# orienteering_clock_rev2.net
KiCad netlist of a schematic drawn in EAGLE
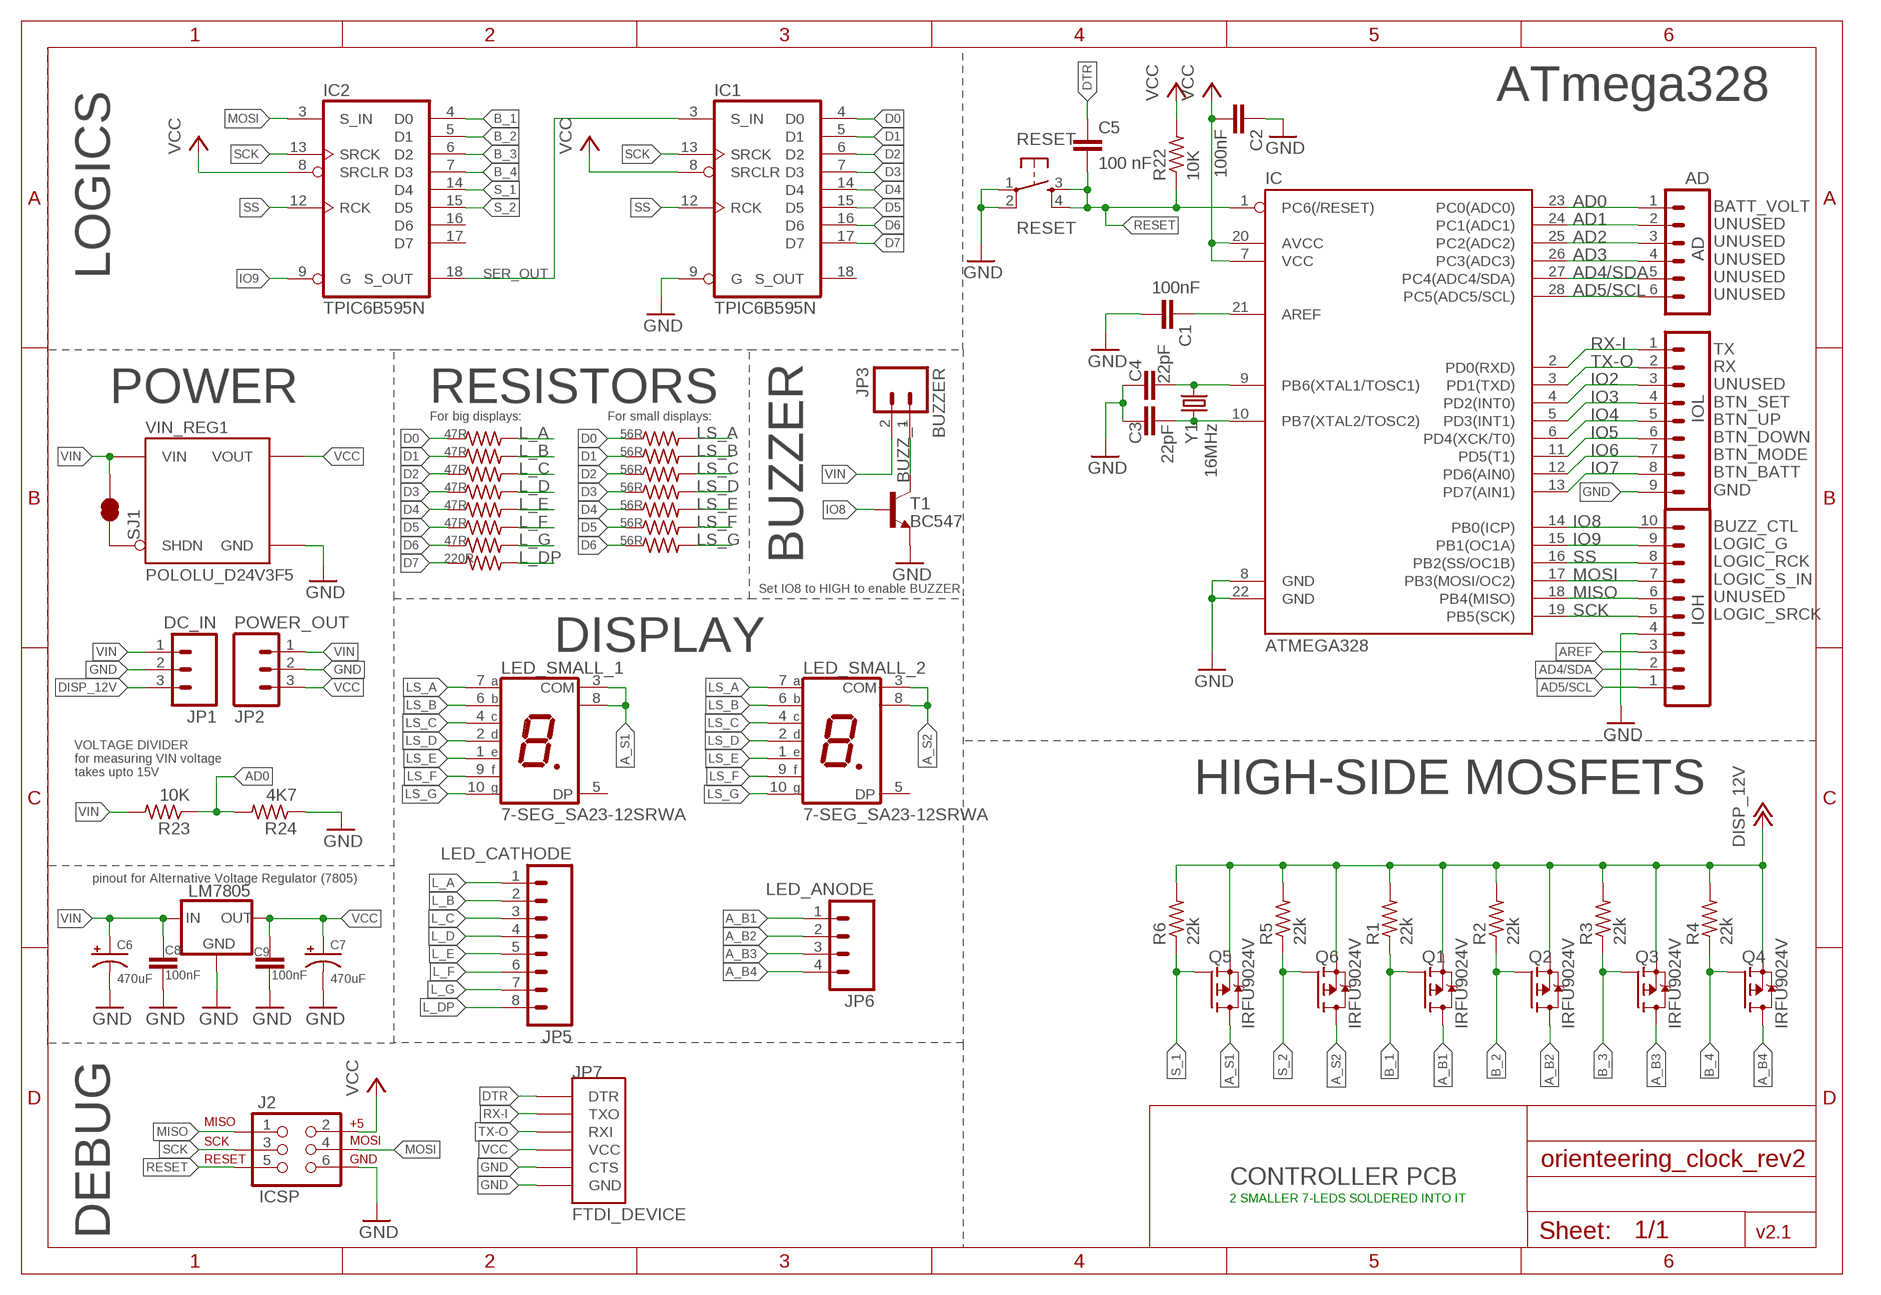
[diagram p0: schematic, sheet 1]

(export (version "E")
  (design (tool "Eeschema 10.0.6"))
  (components
    (comp (ref "AD")
      (value "AD")
      (footprint "eagle-import:1X06-SIP_LOCK")
      (libsource (lib "eagle-import") (part "M06SIP_LOCK"))
    )
    (comp (ref "C1")
      (value "100nF")
      (footprint "eagle-import:CAP-PTH-SMALL")
      (libsource (lib "eagle-import") (part "CAPPTH"))
    )
    (comp (ref "C2")
      (value "100nF")
      (footprint "eagle-import:CAP-PTH-SMALL")
      (libsource (lib "eagle-import") (part "CAPPTH"))
    )
    (comp (ref "C3")
      (value "22pF")
      (footprint "eagle-import:CAP-PTH-SMALL")
      (libsource (lib "eagle-import") (part "SparkFun-Capacitors_CAPPTH"))
    )
    (comp (ref "C4")
      (value "22pF")
      (footprint "eagle-import:CAP-PTH-SMALL")
      (libsource (lib "eagle-import") (part "SparkFun-Capacitors_CAPPTH"))
    )
    (comp (ref "C5")
      (value "100 nF")
      (footprint "eagle-import:CAP-PTH-SMALL")
      (libsource (lib "eagle-import") (part "CAPPTH"))
    )
    (comp (ref "C6")
      (value "470uF")
      (footprint "eagle-import:CPOL-RADIAL-100UF-25V")
      (libsource (lib "eagle-import") (part "CAP_POLPTH1"))
    )
    (comp (ref "C7")
      (value "470uF")
      (footprint "eagle-import:CPOL-RADIAL-100UF-25V")
      (libsource (lib "eagle-import") (part "CAP_POLPTH1"))
    )
    (comp (ref "C8")
      (value "100nF")
      (footprint "eagle-import:CAP-PTH-SMALL")
      (libsource (lib "eagle-import") (part "SparkFun-Passives_CAPPTH"))
    )
    (comp (ref "C9")
      (value "100nF")
      (footprint "eagle-import:CAP-PTH-SMALL")
      (libsource (lib "eagle-import") (part "SparkFun-Passives_CAPPTH"))
    )
    (comp (ref "IC")
      (value "ATMEGA328")
      (footprint "eagle-import:DIL28-3")
      (libsource (lib "eagle-import") (part "ATMEGA328P_PDIP"))
    )
    (comp (ref "IC1")
      (value "TPIC6B595N")
      (footprint "eagle-import:DIL20")
      (libsource (lib "eagle-import") (part "TPIC6B595N"))
    )
    (comp (ref "IC2")
      (value "TPIC6B595N")
      (footprint "eagle-import:DIL20")
      (libsource (lib "eagle-import") (part "TPIC6B595N"))
    )
    (comp (ref "IOH")
      (value "M10LOCK")
      (footprint "eagle-import:1X10_LOCK")
      (libsource (lib "eagle-import") (part "M10LOCK"))
    )
    (comp (ref "IOL")
      (value "M09LOCK")
      (footprint "eagle-import:1X09_LOCK")
      (libsource (lib "eagle-import") (part "M09LOCK"))
    )
    (comp (ref "J2")
      (value "ICSP")
      (footprint "eagle-import:2X3_LOCK")
      (libsource (lib "eagle-import") (part "AVR_SPI_PRG_62X3_LOCK"))
    )
    (comp (ref "JP1")
      (value "DC_IN")
      (footprint "eagle-import:MOLEX-1X3")
      (libsource (lib "eagle-import") (part "M03POLAR"))
    )
    (comp (ref "JP2")
      (value "POWER_OUT")
      (footprint "eagle-import:1X03_LOCK")
      (libsource (lib "eagle-import") (part "M03LOCK"))
    )
    (comp (ref "JP3")
      (value "BUZZER")
      (footprint "eagle-import:1X02_LOCK")
      (libsource (lib "eagle-import") (part "M02LOCK"))
    )
    (comp (ref "JP5")
      (value "LED_CATHODE")
      (footprint "eagle-import:1X08_ROUND")
      (libsource (lib "eagle-import") (part "M08"))
    )
    (comp (ref "JP6")
      (value "LED_ANODE")
      (footprint "eagle-import:1X04")
      (libsource (lib "eagle-import") (part "M04PTH"))
    )
    (comp (ref "JP7")
      (value "FTDI_DEVICE")
      (footprint "eagle-import:FTDI_DEVICE_SIDE")
      (libsource (lib "eagle-import") (part "FTDI_DEVICE"))
    )
    (comp (ref "LED_SMALL_1")
      (value "7-SEG_SA23-12SRWA")
      (footprint "eagle-import:SA23-12SRWA")
      (libsource (lib "eagle-import") (part "7-SEG_SA23-12SRWA"))
    )
    (comp (ref "LED_SMALL_2")
      (value "7-SEG_SA23-12SRWA")
      (footprint "eagle-import:SA23-12SRWA")
      (libsource (lib "eagle-import") (part "7-SEG_SA23-12SRWA"))
    )
    (comp (ref "LM7805")
      (value "78XXS")
      (footprint "eagle-import:78XXS")
      (libsource (lib "eagle-import") (part "78XXS"))
    )
    (comp (ref "Q1")
      (value "IRFU9024V")
      (footprint "eagle-import:TO251AA-V")
      (libsource (lib "eagle-import") (part "IRFU9024V"))
    )
    (comp (ref "Q2")
      (value "IRFU9024V")
      (footprint "eagle-import:TO251AA-V")
      (libsource (lib "eagle-import") (part "IRFU9024V"))
    )
    (comp (ref "Q3")
      (value "IRFU9024V")
      (footprint "eagle-import:TO251AA-V")
      (libsource (lib "eagle-import") (part "IRFU9024V"))
    )
    (comp (ref "Q4")
      (value "IRFU9024V")
      (footprint "eagle-import:TO251AA-V")
      (libsource (lib "eagle-import") (part "IRFU9024V"))
    )
    (comp (ref "Q5")
      (value "IRFU9024V")
      (footprint "eagle-import:TO251AA-V")
      (libsource (lib "eagle-import") (part "IRFU9024V"))
    )
    (comp (ref "Q6")
      (value "IRFU9024V")
      (footprint "eagle-import:TO251AA-V")
      (libsource (lib "eagle-import") (part "IRFU9024V"))
    )
    (comp (ref "R1")
      (value "22k")
      (footprint "eagle-import:0207_5V")
      (libsource (lib "eagle-import") (part "R-US_0207/5V"))
    )
    (comp (ref "R2")
      (value "22k")
      (footprint "eagle-import:0207_5V")
      (libsource (lib "eagle-import") (part "R-US_0207/5V"))
    )
    (comp (ref "R3")
      (value "22k")
      (footprint "eagle-import:0207_5V")
      (libsource (lib "eagle-import") (part "R-US_0207/5V"))
    )
    (comp (ref "R4")
      (value "22k")
      (footprint "eagle-import:0207_5V")
      (libsource (lib "eagle-import") (part "R-US_0207/5V"))
    )
    (comp (ref "R5")
      (value "22k")
      (footprint "eagle-import:0207_5V")
      (libsource (lib "eagle-import") (part "R-US_0207/5V"))
    )
    (comp (ref "R6")
      (value "22k")
      (footprint "eagle-import:0207_5V")
      (libsource (lib "eagle-import") (part "R-US_0207/5V"))
    )
    (comp (ref "R7")
      (value "47R")
      (footprint "eagle-import:0207_10")
      (libsource (lib "eagle-import") (part "R-US_0207/10"))
    )
    (comp (ref "R8")
      (value "47R")
      (footprint "eagle-import:0207_10")
      (libsource (lib "eagle-import") (part "R-US_0207/10"))
    )
    (comp (ref "R9")
      (value "47R")
      (footprint "eagle-import:0207_10")
      (libsource (lib "eagle-import") (part "R-US_0207/10"))
    )
    (comp (ref "R10")
      (value "47R")
      (footprint "eagle-import:0207_10")
      (libsource (lib "eagle-import") (part "R-US_0207/10"))
    )
    (comp (ref "R11")
      (value "47R")
      (footprint "eagle-import:0207_10")
      (libsource (lib "eagle-import") (part "R-US_0207/10"))
    )
    (comp (ref "R12")
      (value "47R")
      (footprint "eagle-import:0207_10")
      (libsource (lib "eagle-import") (part "R-US_0207/10"))
    )
    (comp (ref "R13")
      (value "47R")
      (footprint "eagle-import:0207_10")
      (libsource (lib "eagle-import") (part "R-US_0207/10"))
    )
    (comp (ref "R14")
      (value "56R")
      (footprint "eagle-import:0207_10")
      (libsource (lib "eagle-import") (part "R-US_0207/10"))
    )
    (comp (ref "R15")
      (value "56R")
      (footprint "eagle-import:0207_10")
      (libsource (lib "eagle-import") (part "R-US_0207/10"))
    )
    (comp (ref "R16")
      (value "56R")
      (footprint "eagle-import:0207_10")
      (libsource (lib "eagle-import") (part "R-US_0207/10"))
    )
    (comp (ref "R17")
      (value "56R")
      (footprint "eagle-import:0207_10")
      (libsource (lib "eagle-import") (part "R-US_0207/10"))
    )
    (comp (ref "R18")
      (value "56R")
      (footprint "eagle-import:0207_10")
      (libsource (lib "eagle-import") (part "R-US_0207/10"))
    )
    (comp (ref "R19")
      (value "56R")
      (footprint "eagle-import:0207_10")
      (libsource (lib "eagle-import") (part "R-US_0207/10"))
    )
    (comp (ref "R20")
      (value "56R")
      (footprint "eagle-import:0207_10")
      (libsource (lib "eagle-import") (part "R-US_0207/10"))
    )
    (comp (ref "R21")
      (value "220R")
      (footprint "eagle-import:0207_10")
      (libsource (lib "eagle-import") (part "R-US_0207/10"))
    )
    (comp (ref "R22")
      (value "10K")
      (footprint "eagle-import:0207_10")
      (libsource (lib "eagle-import") (part "R-US_0207/10"))
    )
    (comp (ref "R23")
      (value "10K")
      (footprint "eagle-import:0207_10")
      (libsource (lib "eagle-import") (part "R-US_0207/10"))
    )
    (comp (ref "R24")
      (value "4K7")
      (footprint "eagle-import:0207_10")
      (libsource (lib "eagle-import") (part "R-US_0207/10"))
    )
    (comp (ref "RESET")
      (value "RESET")
      (footprint "eagle-import:TACTILE-PTH")
      (libsource (lib "eagle-import") (part "TAC_SWITCHPTH"))
    )
    (comp (ref "SJ1")
      (value "SHDN_PULLUP")
      (footprint "eagle-import:PAD-JUMPER-2-NC_BY_TRACE_YES_SILK")
      (libsource (lib "eagle-import") (part "JUMPER-PAD-2-NC_BY_TRACE"))
    )
    (comp (ref "T1")
      (value "BC547")
      (footprint "eagle-import:TO92")
      (libsource (lib "eagle-import") (part "BC547"))
    )
    (comp (ref "VIN_REG1")
      (value "POLOLU_D24V3F5")
      (footprint "eagle-import:POLOLU_D24V3F_HC")
      (libsource (lib "eagle-import") (part "POLOLU_D24V3F-HC5"))
    )
    (comp (ref "Y1")
      (value "16MHz")
      (footprint "eagle-import:HC49US")
      (libsource (lib "eagle-import") (part "CRYSTALHC49US"))
    )
  )
  (nets
    (net (code "1") (name "/AD1") (class "Default")
      (node (ref "AD") (pin "2") (pinfunction "2_2") (pintype "passive"))
      (node (ref "IC") (pin "24") (pinfunction "PC1(ADC1)_24") (pintype "bidirectional"))
    )
    (net (code "2") (name "/AD2") (class "Default")
      (node (ref "AD") (pin "3") (pinfunction "3_3") (pintype "passive"))
      (node (ref "IC") (pin "25") (pinfunction "PC2(ADC2)_25") (pintype "bidirectional"))
    )
    (net (code "3") (name "/AD3") (class "Default")
      (node (ref "AD") (pin "4") (pinfunction "4_4") (pintype "passive"))
      (node (ref "IC") (pin "26") (pinfunction "PC3(ADC3)_26") (pintype "bidirectional"))
    )
    (net (code "4") (name "/BUZZ_-") (class "Default")
      (node (ref "JP3") (pin "1") (pinfunction "1_1") (pintype "passive"))
      (node (ref "T1") (pin "3") (pinfunction "C_3") (pintype "passive"))
    )
    (net (code "5") (name "/IO2") (class "Default")
      (node (ref "IC") (pin "4") (pinfunction "PD2(INT0)_4") (pintype "bidirectional"))
      (node (ref "IOL") (pin "3") (pinfunction "3_3") (pintype "passive"))
    )
    (net (code "6") (name "/IO3") (class "Default")
      (node (ref "IC") (pin "5") (pinfunction "PD3(INT1)_5") (pintype "bidirectional"))
      (node (ref "IOL") (pin "4") (pinfunction "4_4") (pintype "passive"))
    )
    (net (code "7") (name "/IO4") (class "Default")
      (node (ref "IC") (pin "6") (pinfunction "PD4(XCK/T0)_6") (pintype "bidirectional"))
      (node (ref "IOL") (pin "5") (pinfunction "5_5") (pintype "passive"))
    )
    (net (code "8") (name "/IO5") (class "Default")
      (node (ref "IC") (pin "11") (pinfunction "PD5(T1)_11") (pintype "bidirectional"))
      (node (ref "IOL") (pin "6") (pinfunction "6_6") (pintype "passive"))
    )
    (net (code "9") (name "/IO6") (class "Default")
      (node (ref "IC") (pin "12") (pinfunction "PD6(AIN0)_12") (pintype "bidirectional"))
      (node (ref "IOL") (pin "7") (pinfunction "7_7") (pintype "passive"))
    )
    (net (code "10") (name "/IO7") (class "Default")
      (node (ref "IC") (pin "13") (pinfunction "PD7(AIN1)_13") (pintype "bidirectional"))
      (node (ref "IOL") (pin "8") (pinfunction "8_8") (pintype "passive"))
    )
    (net (code "11") (name "/SER_OUT") (class "Default")
      (node (ref "IC1") (pin "3") (pinfunction "S_IN_3") (pintype "input"))
      (node (ref "IC2") (pin "18") (pinfunction "S_OUT_18") (pintype "tri_state"))
    )
    (net (code "12") (name "AD0") (class "Default")
      (node (ref "AD") (pin "1") (pinfunction "1_1") (pintype "passive"))
      (node (ref "IC") (pin "23") (pinfunction "PC0(ADC0)_23") (pintype "bidirectional"))
      (node (ref "R23") (pin "1") (pinfunction "1_1") (pintype "passive"))
      (node (ref "R24") (pin "2") (pinfunction "2_2") (pintype "passive"))
    )
    (net (code "13") (name "AD4{slash}SDA") (class "Default")
      (node (ref "AD") (pin "5") (pinfunction "5_5") (pintype "passive"))
      (node (ref "IC") (pin "27") (pinfunction "PC4(ADC4/SDA)_27") (pintype "bidirectional"))
      (node (ref "IOH") (pin "2") (pinfunction "2_2") (pintype "passive"))
    )
    (net (code "14") (name "AD5{slash}SCL") (class "Default")
      (node (ref "AD") (pin "6") (pinfunction "6_6") (pintype "passive"))
      (node (ref "IC") (pin "28") (pinfunction "PC5(ADC5/SCL)_28") (pintype "bidirectional"))
      (node (ref "IOH") (pin "1") (pinfunction "1_1") (pintype "passive"))
    )
    (net (code "15") (name "AREF") (class "Default")
      (node (ref "C1") (pin "1") (pinfunction "1_1") (pintype "passive"))
      (node (ref "IC") (pin "21") (pinfunction "AREF_21") (pintype "bidirectional"))
      (node (ref "IOH") (pin "3") (pinfunction "3_3") (pintype "passive"))
    )
    (net (code "16") (name "A_B1") (class "Default")
      (node (ref "JP6") (pin "1") (pinfunction "1_1") (pintype "passive"))
      (node (ref "Q1") (pin "2") (pinfunction "D_2") (pintype "passive"))
    )
    (net (code "17") (name "A_B2") (class "Default")
      (node (ref "JP6") (pin "2") (pinfunction "2_2") (pintype "passive"))
      (node (ref "Q2") (pin "2") (pinfunction "D_2") (pintype "passive"))
    )
    (net (code "18") (name "A_B3") (class "Default")
      (node (ref "JP6") (pin "3") (pinfunction "3_3") (pintype "passive"))
      (node (ref "Q3") (pin "2") (pinfunction "D_2") (pintype "passive"))
    )
    (net (code "19") (name "A_B4") (class "Default")
      (node (ref "JP6") (pin "4") (pinfunction "4_4") (pintype "passive"))
      (node (ref "Q4") (pin "2") (pinfunction "D_2") (pintype "passive"))
    )
    (net (code "20") (name "A_S1") (class "Default")
      (node (ref "LED_SMALL_1") (pin "3") (pinfunction "COM_3") (pintype "passive"))
      (node (ref "LED_SMALL_1") (pin "8") (pinfunction "COM_8") (pintype "passive"))
      (node (ref "Q5") (pin "2") (pinfunction "D_2") (pintype "passive"))
    )
    (net (code "21") (name "A_S2") (class "Default")
      (node (ref "LED_SMALL_2") (pin "3") (pinfunction "COM_3") (pintype "passive"))
      (node (ref "LED_SMALL_2") (pin "8") (pinfunction "COM_8") (pintype "passive"))
      (node (ref "Q6") (pin "2") (pinfunction "D_2") (pintype "passive"))
    )
    (net (code "22") (name "B_1") (class "Default")
      (node (ref "IC2") (pin "4") (pinfunction "D0_4") (pintype "tri_state"))
      (node (ref "Q1") (pin "1") (pinfunction "G_1") (pintype "passive"))
      (node (ref "R1") (pin "1") (pinfunction "1_1") (pintype "passive"))
    )
    (net (code "23") (name "B_2") (class "Default")
      (node (ref "IC2") (pin "5") (pinfunction "D1_5") (pintype "tri_state"))
      (node (ref "Q2") (pin "1") (pinfunction "G_1") (pintype "passive"))
      (node (ref "R2") (pin "1") (pinfunction "1_1") (pintype "passive"))
    )
    (net (code "24") (name "B_3") (class "Default")
      (node (ref "IC2") (pin "6") (pinfunction "D2_6") (pintype "tri_state"))
      (node (ref "Q3") (pin "1") (pinfunction "G_1") (pintype "passive"))
      (node (ref "R3") (pin "1") (pinfunction "1_1") (pintype "passive"))
    )
    (net (code "25") (name "B_4") (class "Default")
      (node (ref "IC2") (pin "7") (pinfunction "D3_7") (pintype "tri_state"))
      (node (ref "Q4") (pin "1") (pinfunction "G_1") (pintype "passive"))
      (node (ref "R4") (pin "1") (pinfunction "1_1") (pintype "passive"))
    )
    (net (code "26") (name "D0") (class "Default")
      (node (ref "IC1") (pin "4") (pinfunction "D0_4") (pintype "tri_state"))
      (node (ref "R14") (pin "1") (pinfunction "1_1") (pintype "passive"))
      (node (ref "R7") (pin "1") (pinfunction "1_1") (pintype "passive"))
    )
    (net (code "27") (name "D1") (class "Default")
      (node (ref "IC1") (pin "5") (pinfunction "D1_5") (pintype "tri_state"))
      (node (ref "R15") (pin "1") (pinfunction "1_1") (pintype "passive"))
      (node (ref "R8") (pin "1") (pinfunction "1_1") (pintype "passive"))
    )
    (net (code "28") (name "D2") (class "Default")
      (node (ref "IC1") (pin "6") (pinfunction "D2_6") (pintype "tri_state"))
      (node (ref "R16") (pin "1") (pinfunction "1_1") (pintype "passive"))
      (node (ref "R9") (pin "1") (pinfunction "1_1") (pintype "passive"))
    )
    (net (code "29") (name "D3") (class "Default")
      (node (ref "IC1") (pin "7") (pinfunction "D3_7") (pintype "tri_state"))
      (node (ref "R10") (pin "1") (pinfunction "1_1") (pintype "passive"))
      (node (ref "R17") (pin "1") (pinfunction "1_1") (pintype "passive"))
    )
    (net (code "30") (name "D4") (class "Default")
      (node (ref "IC1") (pin "14") (pinfunction "D4_14") (pintype "tri_state"))
      (node (ref "R11") (pin "1") (pinfunction "1_1") (pintype "passive"))
      (node (ref "R18") (pin "1") (pinfunction "1_1") (pintype "passive"))
    )
    (net (code "31") (name "D5") (class "Default")
      (node (ref "IC1") (pin "15") (pinfunction "D5_15") (pintype "tri_state"))
      (node (ref "R12") (pin "1") (pinfunction "1_1") (pintype "passive"))
      (node (ref "R19") (pin "1") (pinfunction "1_1") (pintype "passive"))
    )
    (net (code "32") (name "D6") (class "Default")
      (node (ref "IC1") (pin "16") (pinfunction "D6_16") (pintype "tri_state"))
      (node (ref "R13") (pin "1") (pinfunction "1_1") (pintype "passive"))
      (node (ref "R20") (pin "1") (pinfunction "1_1") (pintype "passive"))
    )
    (net (code "33") (name "D7") (class "Default")
      (node (ref "IC1") (pin "17") (pinfunction "D7_17") (pintype "tri_state"))
      (node (ref "R21") (pin "1") (pinfunction "1_1") (pintype "passive"))
    )
    (net (code "34") (name "DISP_12V") (class "Default")
      (node (ref "JP1") (pin "3") (pinfunction "3_3") (pintype "passive"))
      (node (ref "Q1") (pin "3") (pinfunction "S_3") (pintype "passive"))
      (node (ref "Q2") (pin "3") (pinfunction "S_3") (pintype "passive"))
      (node (ref "Q3") (pin "3") (pinfunction "S_3") (pintype "passive"))
      (node (ref "Q4") (pin "3") (pinfunction "S_3") (pintype "passive"))
      (node (ref "Q5") (pin "3") (pinfunction "S_3") (pintype "passive"))
      (node (ref "Q6") (pin "3") (pinfunction "S_3") (pintype "passive"))
      (node (ref "R1") (pin "2") (pinfunction "2_2") (pintype "passive"))
      (node (ref "R2") (pin "2") (pinfunction "2_2") (pintype "passive"))
      (node (ref "R3") (pin "2") (pinfunction "2_2") (pintype "passive"))
      (node (ref "R4") (pin "2") (pinfunction "2_2") (pintype "passive"))
      (node (ref "R5") (pin "2") (pinfunction "2_2") (pintype "passive"))
      (node (ref "R6") (pin "2") (pinfunction "2_2") (pintype "passive"))
    )
    (net (code "35") (name "DTR") (class "Default")
      (node (ref "C5") (pin "1") (pinfunction "1_1") (pintype "passive"))
      (node (ref "JP7") (pin "P$1") (pinfunction "DTR_P$1") (pintype "bidirectional"))
    )
    (net (code "36") (name "GND") (class "Default")
      (node (ref "C1") (pin "2") (pinfunction "2_2") (pintype "passive"))
      (node (ref "C2") (pin "1") (pinfunction "1_1") (pintype "passive"))
      (node (ref "C3") (pin "1") (pinfunction "1_1") (pintype "passive"))
      (node (ref "C4") (pin "1") (pinfunction "1_1") (pintype "passive"))
      (node (ref "C6") (pin "2") (pinfunction "-_2") (pintype "passive"))
      (node (ref "C7") (pin "2") (pinfunction "-_2") (pintype "passive"))
      (node (ref "C8") (pin "2") (pinfunction "2_2") (pintype "passive"))
      (node (ref "C9") (pin "2") (pinfunction "2_2") (pintype "passive"))
      (node (ref "IC") (pin "22") (pinfunction "GND_22") (pintype "bidirectional"))
      (node (ref "IC") (pin "8") (pinfunction "GND_8") (pintype "bidirectional"))
      (node (ref "IC1") (pin "9") (pinfunction "G_9") (pintype "input"))
      (node (ref "IOH") (pin "4") (pinfunction "4_4") (pintype "passive"))
      (node (ref "IOL") (pin "9") (pinfunction "9_9") (pintype "passive"))
      (node (ref "J2") (pin "6") (pinfunction "6_6") (pintype "passive"))
      (node (ref "JP1") (pin "2") (pinfunction "2_2") (pintype "passive"))
      (node (ref "JP2") (pin "2") (pinfunction "2_2") (pintype "passive"))
      (node (ref "JP7") (pin "P$5") (pinfunction "CTS_P$5") (pintype "bidirectional"))
      (node (ref "JP7") (pin "P$6") (pinfunction "GND_P$6") (pintype "bidirectional"))
      (node (ref "LM7805") (pin "GND") (pinfunction "GND_GND") (pintype "input"))
      (node (ref "R24") (pin "1") (pinfunction "1_1") (pintype "passive"))
      (node (ref "RESET") (pin "1") (pinfunction "1_1") (pintype "passive"))
      (node (ref "RESET") (pin "2") (pinfunction "2_2") (pintype "passive"))
      (node (ref "T1") (pin "1") (pinfunction "E_1") (pintype "passive"))
      (node (ref "VIN_REG1") (pin "G") (pinfunction "GND_G") (pintype "power_in"))
    )
    (net (code "37") (name "IO8") (class "Default")
      (node (ref "IC") (pin "14") (pinfunction "PB0(ICP)_14") (pintype "bidirectional"))
      (node (ref "IOH") (pin "10") (pinfunction "10_10") (pintype "passive"))
      (node (ref "T1") (pin "2") (pinfunction "B_2") (pintype "passive"))
    )
    (net (code "38") (name "IO9") (class "Default")
      (node (ref "IC") (pin "15") (pinfunction "PB1(OC1A)_15") (pintype "bidirectional"))
      (node (ref "IC2") (pin "9") (pinfunction "G_9") (pintype "input"))
      (node (ref "IOH") (pin "9") (pinfunction "9_9") (pintype "passive"))
    )
    (net (code "39") (name "LS_A") (class "Default")
      (node (ref "LED_SMALL_1") (pin "7") (pinfunction "A_7") (pintype "passive"))
      (node (ref "LED_SMALL_2") (pin "7") (pinfunction "A_7") (pintype "passive"))
      (node (ref "R14") (pin "2") (pinfunction "2_2") (pintype "passive"))
    )
    (net (code "40") (name "LS_B") (class "Default")
      (node (ref "LED_SMALL_1") (pin "6") (pinfunction "B_6") (pintype "passive"))
      (node (ref "LED_SMALL_2") (pin "6") (pinfunction "B_6") (pintype "passive"))
      (node (ref "R15") (pin "2") (pinfunction "2_2") (pintype "passive"))
    )
    (net (code "41") (name "LS_C") (class "Default")
      (node (ref "LED_SMALL_1") (pin "4") (pinfunction "C_4") (pintype "passive"))
      (node (ref "LED_SMALL_2") (pin "4") (pinfunction "C_4") (pintype "passive"))
      (node (ref "R16") (pin "2") (pinfunction "2_2") (pintype "passive"))
    )
    (net (code "42") (name "LS_D") (class "Default")
      (node (ref "LED_SMALL_1") (pin "2") (pinfunction "D_2") (pintype "passive"))
      (node (ref "LED_SMALL_2") (pin "2") (pinfunction "D_2") (pintype "passive"))
      (node (ref "R17") (pin "2") (pinfunction "2_2") (pintype "passive"))
    )
    (net (code "43") (name "LS_E") (class "Default")
      (node (ref "LED_SMALL_1") (pin "1") (pinfunction "E_1") (pintype "passive"))
      (node (ref "LED_SMALL_2") (pin "1") (pinfunction "E_1") (pintype "passive"))
      (node (ref "R18") (pin "2") (pinfunction "2_2") (pintype "passive"))
    )
    (net (code "44") (name "LS_F") (class "Default")
      (node (ref "LED_SMALL_1") (pin "9") (pinfunction "F_9") (pintype "passive"))
      (node (ref "LED_SMALL_2") (pin "9") (pinfunction "F_9") (pintype "passive"))
      (node (ref "R19") (pin "2") (pinfunction "2_2") (pintype "passive"))
    )
    (net (code "45") (name "LS_G") (class "Default")
      (node (ref "LED_SMALL_1") (pin "10") (pinfunction "G_10") (pintype "passive"))
      (node (ref "LED_SMALL_2") (pin "10") (pinfunction "G_10") (pintype "passive"))
      (node (ref "R20") (pin "2") (pinfunction "2_2") (pintype "passive"))
    )
    (net (code "46") (name "L_A") (class "Default")
      (node (ref "JP5") (pin "1") (pinfunction "1_1") (pintype "passive"))
      (node (ref "R7") (pin "2") (pinfunction "2_2") (pintype "passive"))
    )
    (net (code "47") (name "L_B") (class "Default")
      (node (ref "JP5") (pin "2") (pinfunction "2_2") (pintype "passive"))
      (node (ref "R8") (pin "2") (pinfunction "2_2") (pintype "passive"))
    )
    (net (code "48") (name "L_C") (class "Default")
      (node (ref "JP5") (pin "3") (pinfunction "3_3") (pintype "passive"))
      (node (ref "R9") (pin "2") (pinfunction "2_2") (pintype "passive"))
    )
    (net (code "49") (name "L_D") (class "Default")
      (node (ref "JP5") (pin "4") (pinfunction "4_4") (pintype "passive"))
      (node (ref "R10") (pin "2") (pinfunction "2_2") (pintype "passive"))
    )
    (net (code "50") (name "L_DP") (class "Default")
      (node (ref "JP5") (pin "8") (pinfunction "8_8") (pintype "passive"))
      (node (ref "R21") (pin "2") (pinfunction "2_2") (pintype "passive"))
    )
    (net (code "51") (name "L_E") (class "Default")
      (node (ref "JP5") (pin "5") (pinfunction "5_5") (pintype "passive"))
      (node (ref "R11") (pin "2") (pinfunction "2_2") (pintype "passive"))
    )
    (net (code "52") (name "L_F") (class "Default")
      (node (ref "JP5") (pin "6") (pinfunction "6_6") (pintype "passive"))
      (node (ref "R12") (pin "2") (pinfunction "2_2") (pintype "passive"))
    )
    (net (code "53") (name "L_G") (class "Default")
      (node (ref "JP5") (pin "7") (pinfunction "7_7") (pintype "passive"))
      (node (ref "R13") (pin "2") (pinfunction "2_2") (pintype "passive"))
    )
    (net (code "54") (name "MISO") (class "Default")
      (node (ref "IC") (pin "18") (pinfunction "PB4(MISO)_18") (pintype "bidirectional"))
      (node (ref "IOH") (pin "6") (pinfunction "6_6") (pintype "passive"))
      (node (ref "J2") (pin "1") (pinfunction "1_1") (pintype "passive"))
    )
    (net (code "55") (name "MOSI") (class "Default")
      (node (ref "IC") (pin "17") (pinfunction "PB3(MOSI/OC2)_17") (pintype "bidirectional"))
      (node (ref "IC2") (pin "3") (pinfunction "S_IN_3") (pintype "input"))
      (node (ref "IOH") (pin "7") (pinfunction "7_7") (pintype "passive"))
      (node (ref "J2") (pin "4") (pinfunction "4_4") (pintype "passive"))
    )
    (net (code "56") (name "Net-(IC-PB6(XTAL1{slash}TOSC1))") (class "Default")
      (node (ref "C4") (pin "2") (pinfunction "2_2") (pintype "passive"))
      (node (ref "IC") (pin "9") (pinfunction "PB6(XTAL1/TOSC1)_9") (pintype "bidirectional"))
      (node (ref "Y1") (pin "2") (pinfunction "2_2") (pintype "passive"))
    )
    (net (code "57") (name "Net-(IC-PB7(XTAL2{slash}TOSC2))") (class "Default")
      (node (ref "C3") (pin "2") (pinfunction "2_2") (pintype "passive"))
      (node (ref "IC") (pin "10") (pinfunction "PB7(XTAL2/TOSC2)_10") (pintype "bidirectional"))
      (node (ref "Y1") (pin "1") (pinfunction "1_1") (pintype "passive"))
    )
    (net (code "58") (name "Net-(VIN_REG1-SHDN)") (class "Default")
      (node (ref "SJ1") (pin "2") (pinfunction "2_2") (pintype "passive"))
      (node (ref "VIN_REG1") (pin "S") (pinfunction "SHDN_S") (pintype "input"))
    )
    (net (code "59") (name "RESET") (class "Default")
      (node (ref "C5") (pin "2") (pinfunction "2_2") (pintype "passive"))
      (node (ref "IC") (pin "1") (pinfunction "PC6(/RESET)_1") (pintype "bidirectional"))
      (node (ref "J2") (pin "5") (pinfunction "5_5") (pintype "passive"))
      (node (ref "R22") (pin "1") (pinfunction "1_1") (pintype "passive"))
      (node (ref "RESET") (pin "3") (pinfunction "3_3") (pintype "passive"))
      (node (ref "RESET") (pin "4") (pinfunction "4_4") (pintype "passive"))
    )
    (net (code "60") (name "RX-I") (class "Default")
      (node (ref "IC") (pin "2") (pinfunction "PD0(RXD)_2") (pintype "bidirectional"))
      (node (ref "IOL") (pin "1") (pinfunction "1_1") (pintype "passive"))
      (node (ref "JP7") (pin "P$2") (pinfunction "TXO_P$2") (pintype "bidirectional"))
    )
    (net (code "61") (name "SCK") (class "Default")
      (node (ref "IC") (pin "19") (pinfunction "PB5(SCK)_19") (pintype "bidirectional"))
      (node (ref "IC1") (pin "13") (pinfunction "SRCK_13") (pintype "input"))
      (node (ref "IC2") (pin "13") (pinfunction "SRCK_13") (pintype "input"))
      (node (ref "IOH") (pin "5") (pinfunction "5_5") (pintype "passive"))
      (node (ref "J2") (pin "3") (pinfunction "3_3") (pintype "passive"))
    )
    (net (code "62") (name "SS") (class "Default")
      (node (ref "IC") (pin "16") (pinfunction "PB2(SS/OC1B)_16") (pintype "bidirectional"))
      (node (ref "IC1") (pin "12") (pinfunction "RCK_12") (pintype "input"))
      (node (ref "IC2") (pin "12") (pinfunction "RCK_12") (pintype "input"))
      (node (ref "IOH") (pin "8") (pinfunction "8_8") (pintype "passive"))
    )
    (net (code "63") (name "S_1") (class "Default")
      (node (ref "IC2") (pin "14") (pinfunction "D4_14") (pintype "tri_state"))
      (node (ref "Q5") (pin "1") (pinfunction "G_1") (pintype "passive"))
      (node (ref "R6") (pin "1") (pinfunction "1_1") (pintype "passive"))
    )
    (net (code "64") (name "S_2") (class "Default")
      (node (ref "IC2") (pin "15") (pinfunction "D5_15") (pintype "tri_state"))
      (node (ref "Q6") (pin "1") (pinfunction "G_1") (pintype "passive"))
      (node (ref "R5") (pin "1") (pinfunction "1_1") (pintype "passive"))
    )
    (net (code "65") (name "TX-O") (class "Default")
      (node (ref "IC") (pin "3") (pinfunction "PD1(TXD)_3") (pintype "bidirectional"))
      (node (ref "IOL") (pin "2") (pinfunction "2_2") (pintype "passive"))
      (node (ref "JP7") (pin "P$3") (pinfunction "RXI_P$3") (pintype "bidirectional"))
    )
    (net (code "66") (name "VCC") (class "Default")
      (node (ref "C2") (pin "2") (pinfunction "2_2") (pintype "passive"))
      (node (ref "C7") (pin "1") (pinfunction "+_1") (pintype "passive"))
      (node (ref "C9") (pin "1") (pinfunction "1_1") (pintype "passive"))
      (node (ref "IC") (pin "20") (pinfunction "AVCC_20") (pintype "bidirectional"))
      (node (ref "IC") (pin "7") (pinfunction "VCC_7") (pintype "bidirectional"))
      (node (ref "IC1") (pin "8") (pinfunction "SRCLR_8") (pintype "input"))
      (node (ref "IC2") (pin "8") (pinfunction "SRCLR_8") (pintype "input"))
      (node (ref "J2") (pin "2") (pinfunction "2_2") (pintype "passive"))
      (node (ref "JP2") (pin "3") (pinfunction "3_3") (pintype "passive"))
      (node (ref "JP7") (pin "P$4") (pinfunction "VCC_P$4") (pintype "bidirectional"))
      (node (ref "LM7805") (pin "OUT") (pinfunction "OUT_OUT") (pintype "passive"))
      (node (ref "R22") (pin "2") (pinfunction "2_2") (pintype "passive"))
      (node (ref "VIN_REG1") (pin "O") (pinfunction "VOUT_O") (pintype "output"))
    )
    (net (code "67") (name "VIN") (class "Default")
      (node (ref "C6") (pin "1") (pinfunction "+_1") (pintype "passive"))
      (node (ref "C8") (pin "1") (pinfunction "1_1") (pintype "passive"))
      (node (ref "JP1") (pin "1") (pinfunction "1_1") (pintype "passive"))
      (node (ref "JP2") (pin "1") (pinfunction "1_1") (pintype "passive"))
      (node (ref "JP3") (pin "2") (pinfunction "2_2") (pintype "passive"))
      (node (ref "LM7805") (pin "IN") (pinfunction "IN_IN") (pintype "input"))
      (node (ref "R23") (pin "2") (pinfunction "2_2") (pintype "passive"))
      (node (ref "SJ1") (pin "1") (pinfunction "1_1") (pintype "passive"))
      (node (ref "VIN_REG1") (pin "I") (pinfunction "VIN_I") (pintype "power_in"))
    )
    (net (code "68") (name "unconnected-(IC1A-S_OUT-Pad18)") (class "Default")
      (node (ref "IC1") (pin "18") (pinfunction "S_OUT_18") (pintype "tri_state"))
    )
    (net (code "69") (name "unconnected-(IC2A-D6-Pad16)") (class "Default")
      (node (ref "IC2") (pin "16") (pinfunction "D6_16") (pintype "tri_state"))
    )
    (net (code "70") (name "unconnected-(IC2A-D7-Pad17)") (class "Default")
      (node (ref "IC2") (pin "17") (pinfunction "D7_17") (pintype "tri_state"))
    )
    (net (code "71") (name "unconnected-(LED_SMALL_1-DP-Pad5)") (class "Default")
      (node (ref "LED_SMALL_1") (pin "5") (pinfunction "DP_5") (pintype "passive"))
    )
    (net (code "72") (name "unconnected-(LED_SMALL_2-DP-Pad5)") (class "Default")
      (node (ref "LED_SMALL_2") (pin "5") (pinfunction "DP_5") (pintype "passive"))
    )
  )
)
